# WiredRemoteController.net
KiCad netlist of a schematic drawn in Altium Designer
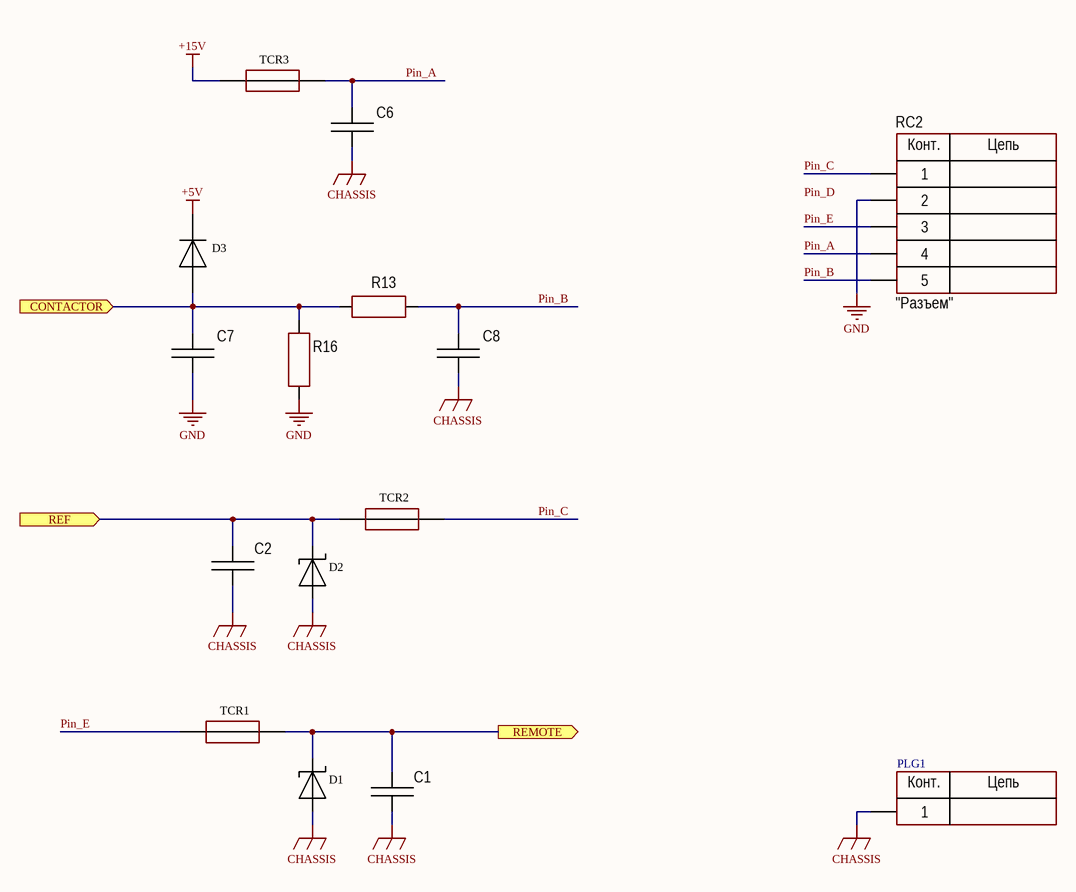
[diagram p0: WiredRemoteController.SchDoc]

(export (version "E")
  (design (tool "Eeschema 10.0.6"))
  (components
    (comp (ref "C1")
      (value "~")
      (footprint "FP_lib_PCB:CAPC4564X22M")
      (fields
        (field (name "MANUFACTURER") "Yageo")
        (field (name "PARTNUMBER") "CC1206KRX7R9BB104")
        (field (name "VALUEMANUFACTURERPARTNUMBER") "Ceramic capacitor, 0.1μF, 1825")
      )
      (libsource (lib "Capacitor") (part "Ceramic_1206"))
    )
    (comp (ref "C2")
      (value "~")
      (footprint "FP_lib_PCB:CAPC4564X22M")
      (fields
        (field (name "MANUFACTURER") "Yageo")
        (field (name "PARTNUMBER") "CC1206KRX7R9BB104")
        (field (name "VALUEMANUFACTURERPARTNUMBER") "Ceramic capacitor, 0.1μF, 1825")
      )
      (libsource (lib "Capacitor") (part "Ceramic_1206"))
    )
    (comp (ref "C6")
      (value "~")
      (footprint "FP_lib_PCB:CAPC4564X22M")
      (fields
        (field (name "MANUFACTURER") "Yageo")
        (field (name "PARTNUMBER") "CC1206KRX7R9BB104")
        (field (name "VALUEMANUFACTURERPARTNUMBER") "Ceramic capacitor, 0.1μF, 1825")
      )
      (libsource (lib "Capacitor") (part "Ceramic_1206"))
    )
    (comp (ref "C7")
      (value "~")
      (footprint "StandardCase:CAP: 1206")
      (fields
        (field (name "MANUFACTURER") "Yageo")
        (field (name "PARTNUMBER") "CC1206KRX7R9BB104")
        (field (name "VALUEMANUFACTURERPARTNUMBER") "Ceramic capacitor, 0.1μF, 1206")
      )
      (libsource (lib "Capacitor") (part "Ceramic_1206"))
    )
    (comp (ref "C8")
      (value "~")
      (footprint "FP_lib_PCB:CAPC4564X22M")
      (fields
        (field (name "MANUFACTURER") "Yageo")
        (field (name "PARTNUMBER") "CC1206KRX7R9BB104")
        (field (name "VALUEMANUFACTURERPARTNUMBER") "Ceramic capacitor, 0.1μF, 1825")
      )
      (libsource (lib "Capacitor") (part "Ceramic_1206"))
    )
    (comp (ref "D1")
      (value "~")
      (footprint "StandardCase:DIODE: SMC")
      (fields
        (field (name "VALUEMANUFACTURERPARTNUMBER") "SMCJ15A, SMC")
        (field (name "PARTNUMBER") "SMCJ15A")
      )
      (libsource (lib "FP_lib_SCH") (part "SMCJ15A"))
    )
    (comp (ref "D2")
      (value "~")
      (footprint "StandardCase:DIODE: SMC")
      (fields
        (field (name "VALUEMANUFACTURERPARTNUMBER") "SMCJ15A, SMC")
        (field (name "PARTNUMBER") "SMCJ15A")
      )
      (libsource (lib "FP_lib_SCH") (part "SMCJ15A"))
    )
    (comp (ref "D3")
      (value "~")
      (footprint "StandardCase:SOT23")
      (fields
        (field (name "VALUEMANUFACTURERPARTNUMBER") "MMBD4148, SOT23")
        (field (name "PARTNUMBER") "MMBD4148")
      )
      (libsource (lib "FP_lib_SCH") (part "MMBD4148"))
    )
    (comp (ref "PLG1")
      (value "PLG1")
      (footprint "FP_lib_PCB:PLG1")
      (libsource (lib "FP_lib_SCH") (part "PLG1"))
    )
    (comp (ref "R13")
      (value "~")
      (footprint "StandardCase:RES: 1206")
      (fields
        (field (name "MANUFACTURER") "Yageo")
        (field (name "PARTNUMBER") "RC1206JR-07100RL")
        (field (name "VALUEMANUFACTURERPARTNUMBER") "Resistor, 10K, 1206")
      )
      (libsource (lib "Resistor") (part "Resistor_1206"))
    )
    (comp (ref "R16")
      (value "~")
      (footprint "StandardCase:RES: 1206")
      (fields
        (field (name "MANUFACTURER") "Yageo")
        (field (name "PARTNUMBER") "RC1206JR-07100RL")
        (field (name "VALUEMANUFACTURERPARTNUMBER") "Resistor, 4.99K, 1206")
      )
      (libsource (lib "") (part "Resistor_1206_1"))
    )
    (comp (ref "RC2")
      (value "~")
      (footprint "FP_lib_PCB:MOLEX 39-30-3056")
      (fields
        (field (name "MANUFACTURER") "MOLEX")
        (field (name "VALUEMANUFACTURERPARTNUMBER") "Connector, MOLEX, 39-30-3056, 5pin")
        (field (name "PARTNUMBER") "39-30-3056")
        (field (name "COMMENTTEXT") "\"Разъем\"")
      )
      (libsource (lib "Connector") (part "PBS-5"))
    )
    (comp (ref "TCR1")
      (value "~")
      (footprint "FP_lib_PCB:TRF250-120T-B-0.5")
      (fields (field (name "VALUEMANUFACTURERPARTNUMBER") "TRF250-120T-B-0.5"))
      (libsource (lib "FP_lib_SCH") (part "TRF250-120T-B-0.5"))
    )
    (comp (ref "TCR2")
      (value "~")
      (footprint "FP_lib_PCB:TRF250-120T-B-0.5")
      (fields (field (name "VALUEMANUFACTURERPARTNUMBER") "TRF250-120T-B-0.5"))
      (libsource (lib "") (part "TRF250-120T-B-0.5_1"))
    )
    (comp (ref "TCR3")
      (value "~")
      (footprint "FP_lib_PCB:TRF250-120T-B-0.5")
      (fields (field (name "VALUEMANUFACTURERPARTNUMBER") "TRF250-120T-B-0.5"))
      (libsource (lib "") (part "TRF250-120T-B-0.5_1"))
    )
  )
  (nets
    (net (code "1") (name "+5V") (class "Default")
      (node (ref "D3") (pin "3") (pinfunction "3_3") (pintype "passive"))
    )
    (net (code "2") (name "+15V") (class "Default")
      (node (ref "TCR3") (pin "1") (pinfunction "1_1") (pintype "passive"))
    )
    (net (code "3") (name "/CONTACTOR") (class "Default")
      (node (ref "C7") (pin "2") (pinfunction "2_2") (pintype "power_in"))
      (node (ref "D3") (pin "1") (pinfunction "1_1") (pintype "passive"))
      (node (ref "R13") (pin "2") (pinfunction "2_2") (pintype "passive"))
      (node (ref "R16") (pin "2") (pinfunction "2_2") (pintype "passive"))
    )
    (net (code "4") (name "/Pin_A") (class "Default")
      (node (ref "C6") (pin "2") (pinfunction "2_2") (pintype "power_in"))
      (node (ref "RC2") (pin "4") (pinfunction "4_4") (pintype "power_in"))
      (node (ref "TCR3") (pin "2") (pinfunction "2_2") (pintype "passive"))
    )
    (net (code "5") (name "/Pin_B") (class "Default")
      (node (ref "C8") (pin "2") (pinfunction "2_2") (pintype "power_in"))
      (node (ref "R13") (pin "1") (pinfunction "1_1") (pintype "passive"))
      (node (ref "RC2") (pin "5") (pinfunction "5_5") (pintype "power_in"))
    )
    (net (code "6") (name "/Pin_C") (class "Default")
      (node (ref "RC2") (pin "1") (pinfunction "1_1") (pintype "passive"))
      (node (ref "TCR2") (pin "2") (pinfunction "2_2") (pintype "passive"))
    )
    (net (code "8") (name "/Pin_E") (class "Default")
      (node (ref "RC2") (pin "3") (pinfunction "3_3") (pintype "power_in"))
      (node (ref "TCR1") (pin "2") (pinfunction "2_2") (pintype "passive"))
    )
    (net (code "9") (name "/REF") (class "Default")
      (node (ref "C2") (pin "2") (pinfunction "2_2") (pintype "power_in"))
      (node (ref "D2") (pin "2") (pinfunction "C_2") (pintype "passive"))
      (node (ref "TCR2") (pin "1") (pinfunction "1_1") (pintype "passive"))
    )
    (net (code "10") (name "/REMOTE") (class "Default")
      (node (ref "C1") (pin "2") (pinfunction "2_2") (pintype "power_in"))
      (node (ref "D1") (pin "2") (pinfunction "C_2") (pintype "passive"))
      (node (ref "TCR1") (pin "1") (pinfunction "1_1") (pintype "passive"))
    )
    (net (code "11") (name "CHASSIS") (class "Default")
      (node (ref "C1") (pin "1") (pinfunction "1_1") (pintype "power_in"))
      (node (ref "C2") (pin "1") (pinfunction "1_1") (pintype "power_in"))
      (node (ref "C6") (pin "1") (pinfunction "1_1") (pintype "power_in"))
      (node (ref "C8") (pin "1") (pinfunction "1_1") (pintype "power_in"))
      (node (ref "D1") (pin "1") (pinfunction "A_1") (pintype "passive"))
      (node (ref "D2") (pin "1") (pinfunction "A_1") (pintype "passive"))
      (node (ref "PLG1") (pin "1") (pinfunction "1_1") (pintype "passive"))
    )
    (net (code "12") (name "GND") (class "Default")
      (node (ref "C7") (pin "1") (pinfunction "1_1") (pintype "power_in"))
      (node (ref "R16") (pin "1") (pinfunction "1_1") (pintype "passive"))
      (node (ref "RC2") (pin "2") (pinfunction "2_2") (pintype "passive"))
    )
  )
)
